# 16_RK3588_VCCIO6.net
KiCad netlist of a schematic drawn in Altium Designer
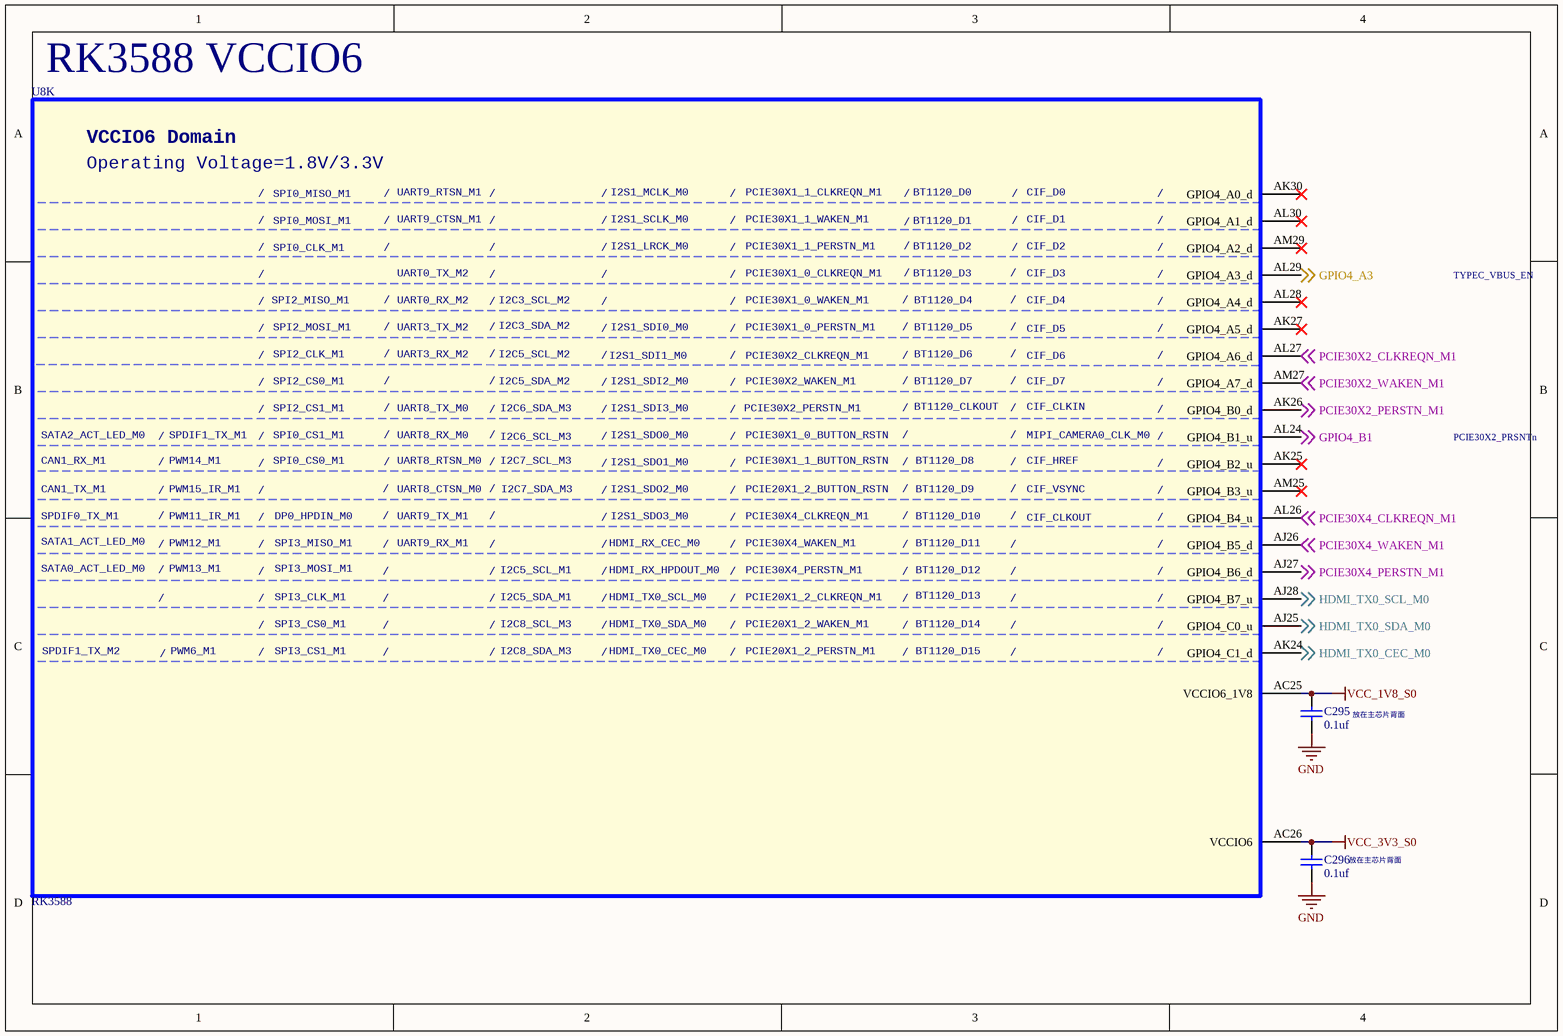
[diagram p0: 16.RK3588_VCCIO6.SchDoc]

(export (version "E")
  (design (tool "Eeschema 10.0.6"))
  (components
    (comp (ref "C295")
      (value "0.1uf")
      (footprint "0.PCB1:C0201_L")
      (description "贴片电容/MLCC电容")
      (libsource (lib "RK3588") (part "C"))
    )
    (comp (ref "C296")
      (value "0.1uf")
      (footprint "0.PCB1:C0201_L")
      (description "贴片电容/MLCC电容")
      (libsource (lib "RK3588") (part "C"))
    )
    (comp (ref "U8")
      (value "RK3588")
      (footprint "0.PCB1:BGA1088_23R00X23R00X2R00")
      (description "ROCKCHIP SOC")
      (libsource (lib "RK3588") (part "SOC_RK3588"))
    )
  )
  (nets
    (net (code "1") (name "GND") (class "Default")
      (node (ref "C295") (pin "1") (pinfunction "1_1") (pintype "passive"))
      (node (ref "C296") (pin "1") (pinfunction "1_1") (pintype "passive"))
    )
    (net (code "2") (name "GPIO4_A3") (class "Default")
      (node (ref "U8") (pin "AL29") (pinfunction "GPIO4_A3_d_AL29") (pintype "passive"))
    )
    (net (code "3") (name "GPIO4_B1") (class "Default")
      (node (ref "U8") (pin "AL24") (pinfunction "GPIO4_B1_u_AL24") (pintype "passive"))
    )
    (net (code "4") (name "HDMI_TX0_CEC_M0") (class "Default")
      (node (ref "U8") (pin "AK24") (pinfunction "GPIO4_C1_d_AK24") (pintype "passive"))
    )
    (net (code "5") (name "HDMI_TX0_SCL_M0") (class "Default")
      (node (ref "U8") (pin "AJ28") (pinfunction "GPIO4_B7_u_AJ28") (pintype "passive"))
    )
    (net (code "6") (name "HDMI_TX0_SDA_M0") (class "Default")
      (node (ref "U8") (pin "AJ25") (pinfunction "GPIO4_C0_u_AJ25") (pintype "passive"))
    )
    (net (code "7") (name "PCIE30X2_CLKREQN_M1") (class "Default")
      (node (ref "U8") (pin "AL27") (pinfunction "GPIO4_A6_d_AL27") (pintype "passive"))
    )
    (net (code "8") (name "PCIE30X2_PERSTN_M1") (class "Default")
      (node (ref "U8") (pin "AK26") (pinfunction "GPIO4_B0_d_AK26") (pintype "passive"))
    )
    (net (code "9") (name "PCIE30X2_WAKEN_M1") (class "Default")
      (node (ref "U8") (pin "AM27") (pinfunction "GPIO4_A7_d_AM27") (pintype "passive"))
    )
    (net (code "10") (name "PCIE30X4_CLKREQN_M1") (class "Default")
      (node (ref "U8") (pin "AL26") (pinfunction "GPIO4_B4_u_AL26") (pintype "passive"))
    )
    (net (code "11") (name "PCIE30X4_PERSTN_M1") (class "Default")
      (node (ref "U8") (pin "AJ27") (pinfunction "GPIO4_B6_d_AJ27") (pintype "passive"))
    )
    (net (code "12") (name "PCIE30X4_WAKEN_M1") (class "Default")
      (node (ref "U8") (pin "AJ26") (pinfunction "GPIO4_B5_d_AJ26") (pintype "passive"))
    )
    (net (code "13") (name "VCC_1V8_S0") (class "Default")
      (node (ref "C295") (pin "2") (pinfunction "2_2") (pintype "passive"))
      (node (ref "U8") (pin "AC25") (pinfunction "VCCIO6_1V8_AC25") (pintype "passive"))
    )
    (net (code "14") (name "VCC_3V3_S0") (class "Default")
      (node (ref "C296") (pin "2") (pinfunction "2_2") (pintype "passive"))
      (node (ref "U8") (pin "AC26") (pinfunction "VCCIO6_AC26") (pintype "passive"))
    )
    (net (code "15") (name "unconnected-(U8K-GPIO4_A0_d-PadAK30)") (class "Default")
      (node (ref "U8") (pin "AK30") (pinfunction "GPIO4_A0_d_AK30") (pintype "passive+no_connect"))
    )
    (net (code "16") (name "unconnected-(U8K-GPIO4_A1_d-PadAL30)") (class "Default")
      (node (ref "U8") (pin "AL30") (pinfunction "GPIO4_A1_d_AL30") (pintype "passive+no_connect"))
    )
    (net (code "17") (name "unconnected-(U8K-GPIO4_A2_d-PadAM29)") (class "Default")
      (node (ref "U8") (pin "AM29") (pinfunction "GPIO4_A2_d_AM29") (pintype "passive+no_connect"))
    )
    (net (code "18") (name "unconnected-(U8K-GPIO4_A4_d-PadAL28)") (class "Default")
      (node (ref "U8") (pin "AL28") (pinfunction "GPIO4_A4_d_AL28") (pintype "passive+no_connect"))
    )
    (net (code "19") (name "unconnected-(U8K-GPIO4_A5_d-PadAK27)") (class "Default")
      (node (ref "U8") (pin "AK27") (pinfunction "GPIO4_A5_d_AK27") (pintype "passive+no_connect"))
    )
    (net (code "20") (name "unconnected-(U8K-GPIO4_B2_u-PadAK25)") (class "Default")
      (node (ref "U8") (pin "AK25") (pinfunction "GPIO4_B2_u_AK25") (pintype "passive+no_connect"))
    )
    (net (code "21") (name "unconnected-(U8K-GPIO4_B3_u-PadAM25)") (class "Default")
      (node (ref "U8") (pin "AM25") (pinfunction "GPIO4_B3_u_AM25") (pintype "passive+no_connect"))
    )
  )
)
